# Small_Whole_House_Power_Meter_STPM34_v0_.net
KiCad netlist of a schematic drawn in EAGLE
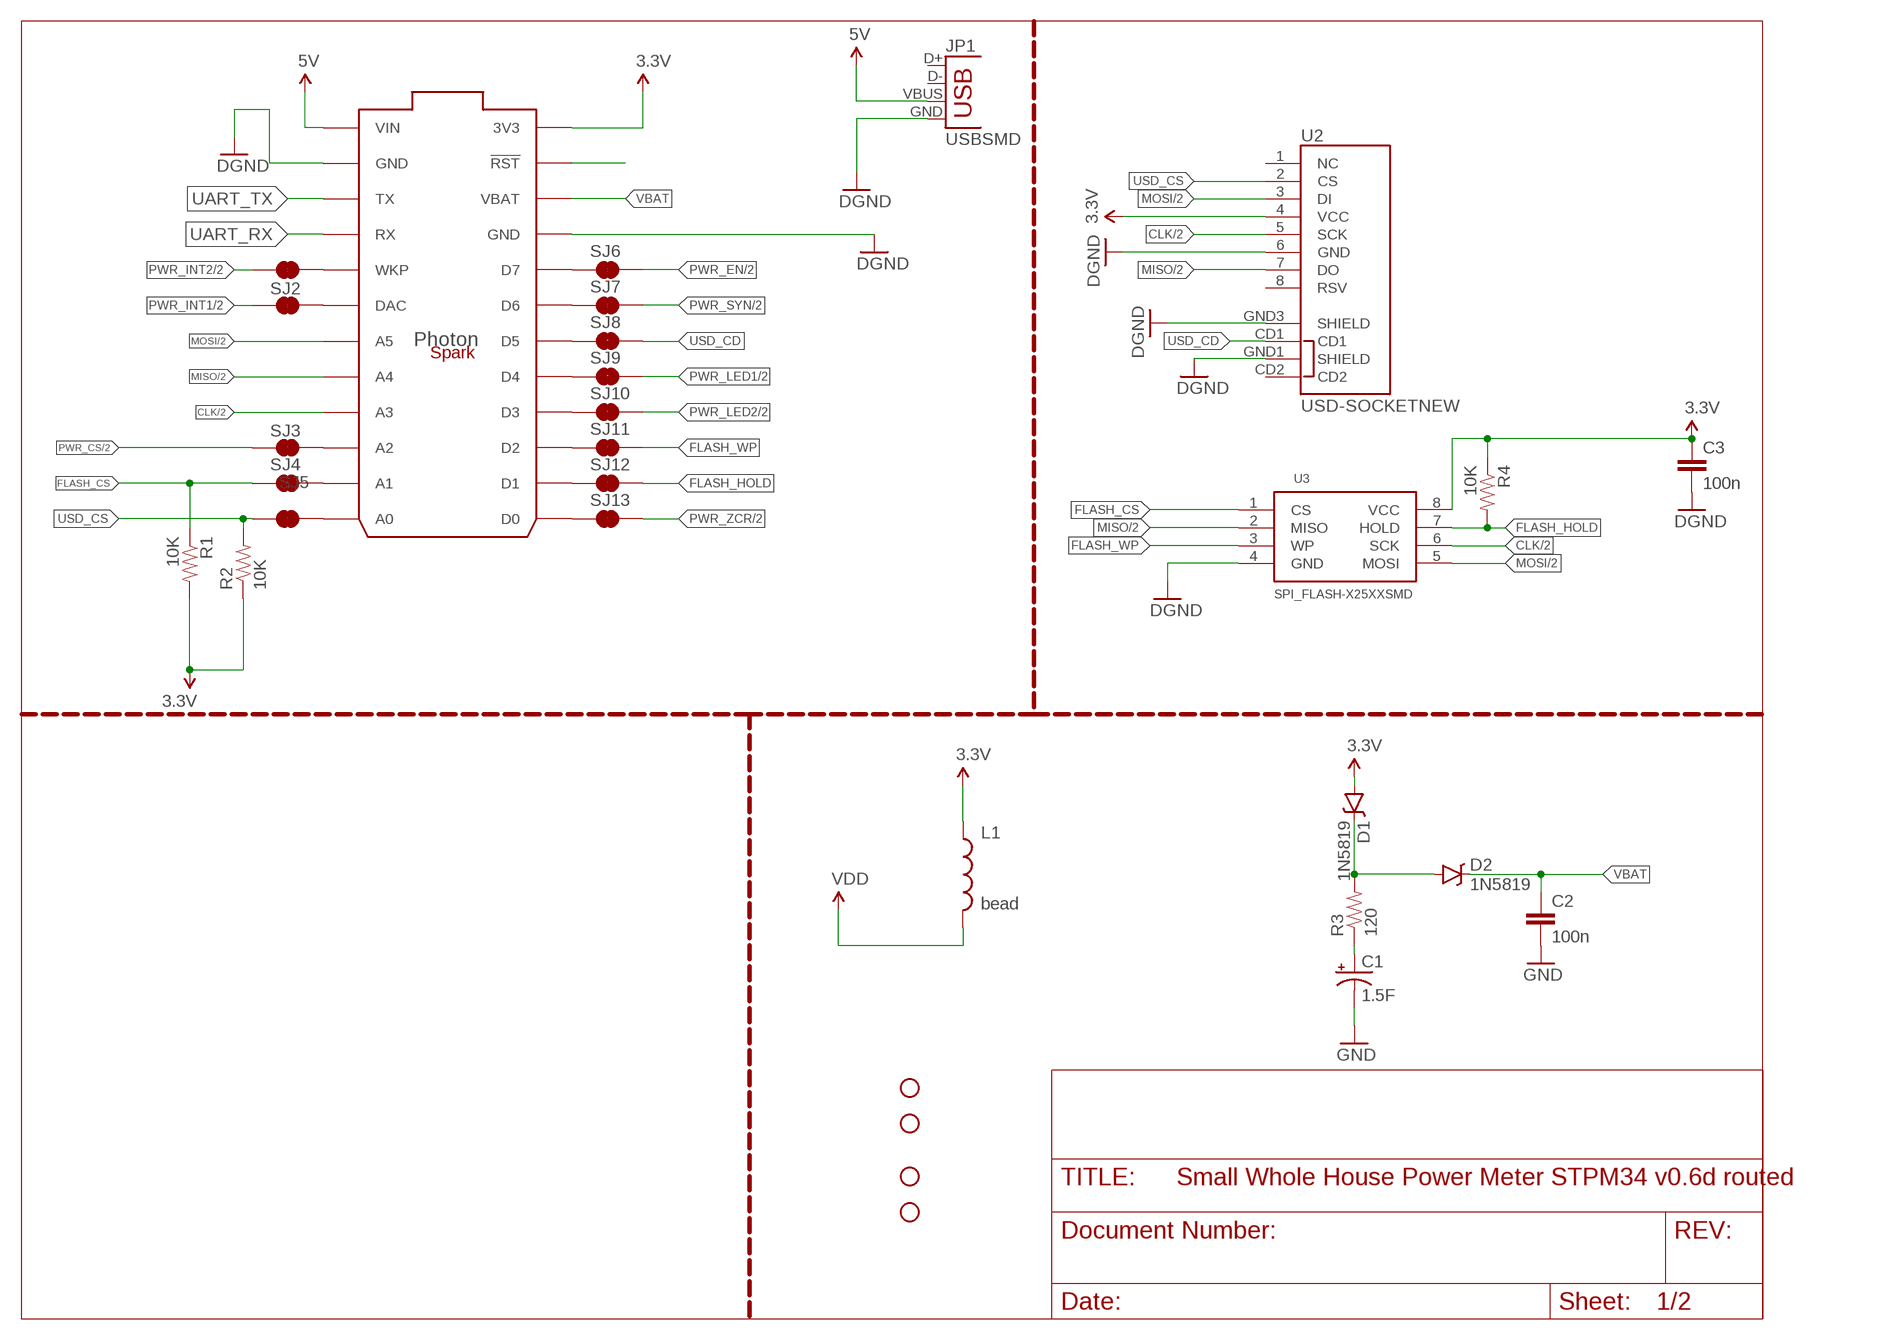
[diagram p0: schematic, sheet 1]
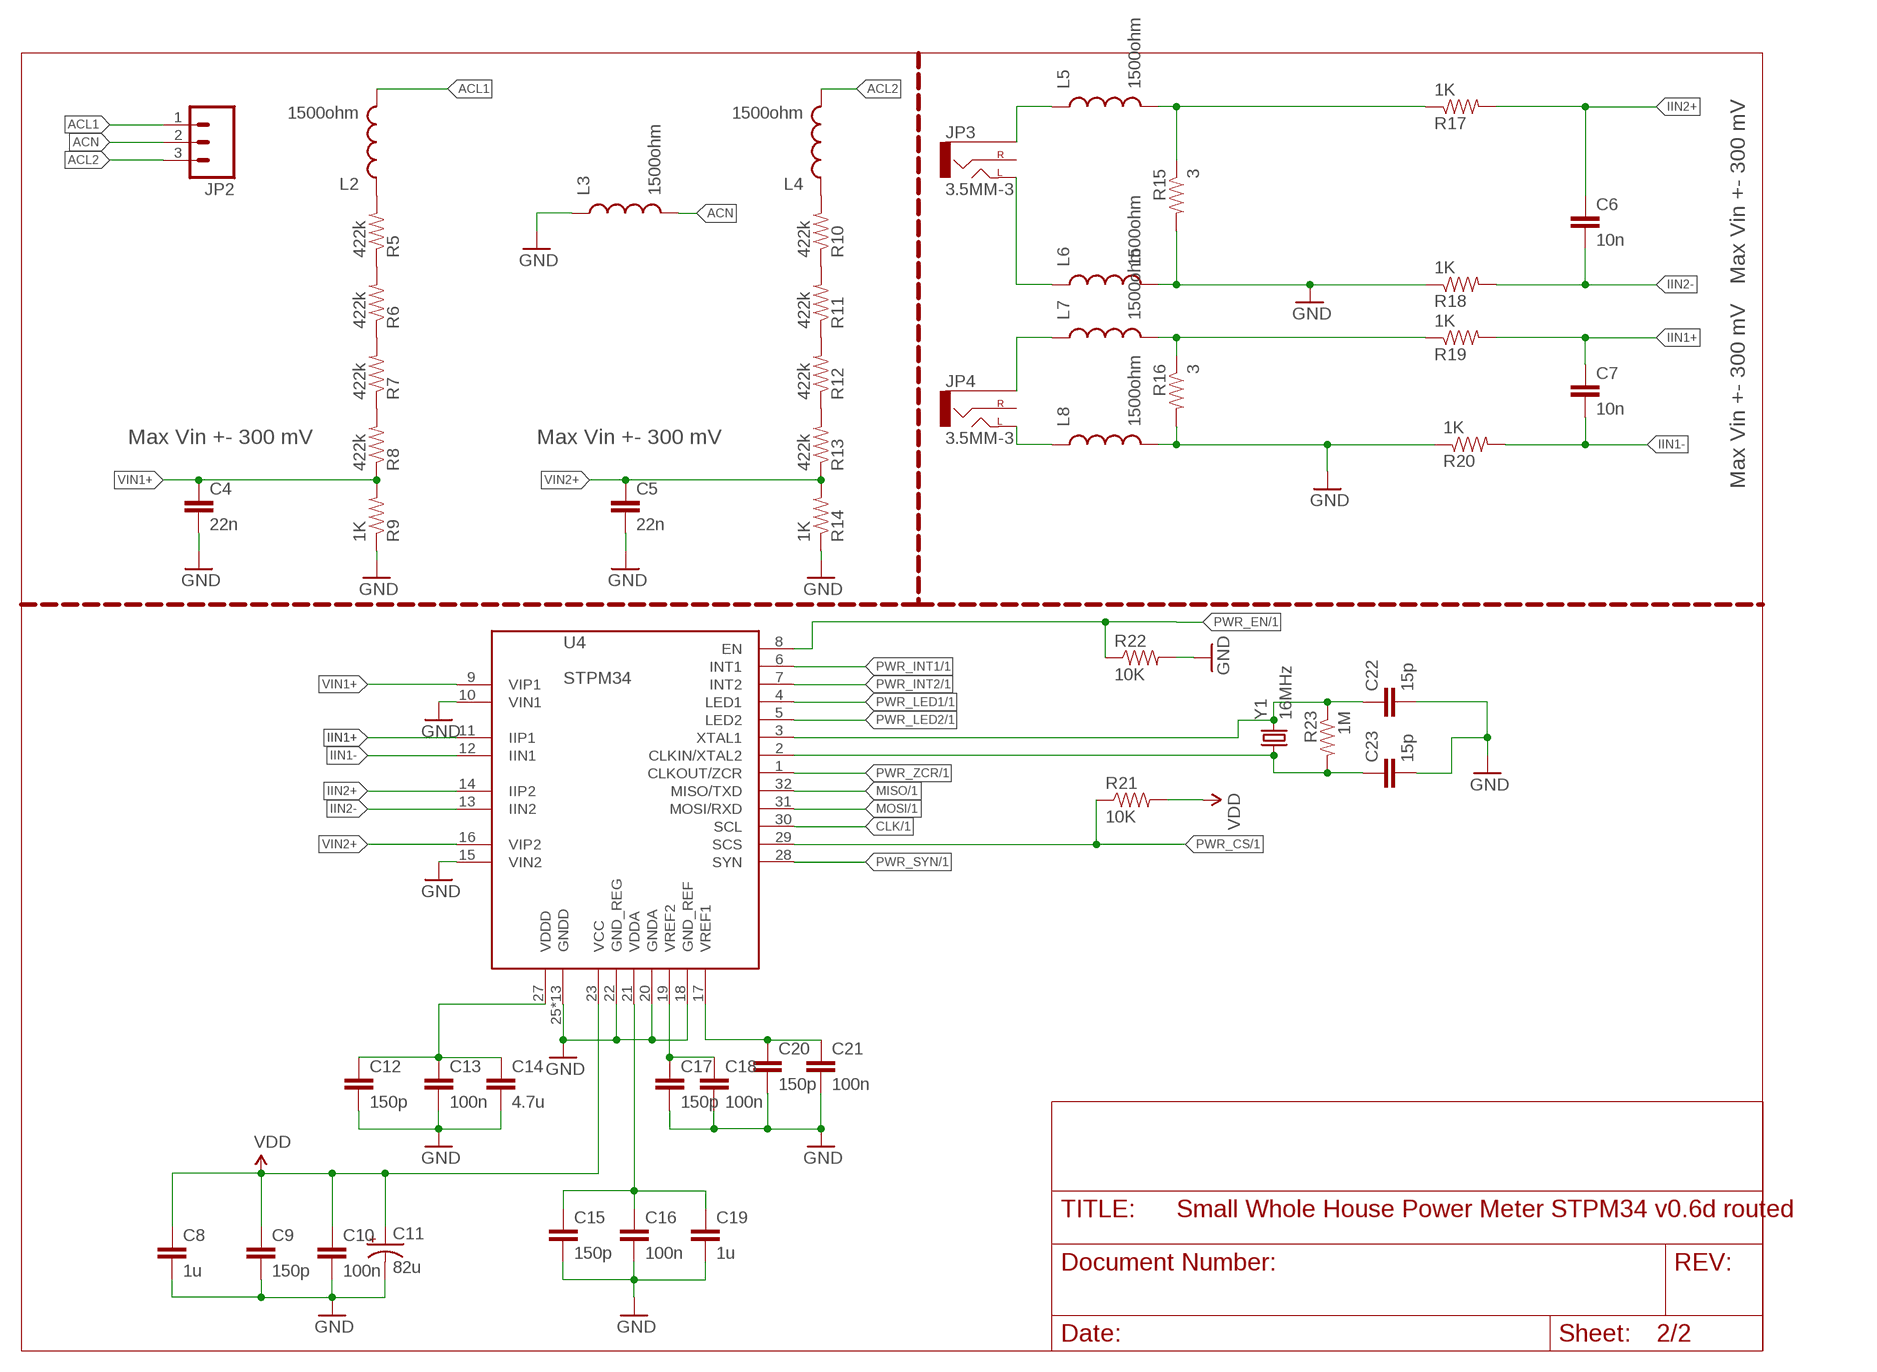
[diagram p1: schematic, sheet 2]

(export (version "E")
  (design (tool "Eeschema 10.0.6"))
  (components
    (comp (ref "C4")
      (value "22n")
      (footprint "eagle-import:0603-CAP")
      (libsource (lib "eagle-import") (part "CAP0603-CAP"))
    )
    (comp (ref "C5")
      (value "22n")
      (footprint "eagle-import:0603-CAP")
      (libsource (lib "eagle-import") (part "CAP0603-CAP"))
    )
    (comp (ref "C6")
      (value "10n")
      (footprint "eagle-import:0603-CAP")
      (libsource (lib "eagle-import") (part "CAP0603-CAP"))
    )
    (comp (ref "C7")
      (value "10n")
      (footprint "eagle-import:0603-CAP")
      (libsource (lib "eagle-import") (part "CAP0603-CAP"))
    )
    (comp (ref "C8")
      (value "1u")
      (footprint "eagle-import:0603-CAP")
      (libsource (lib "eagle-import") (part "CAP0603-CAP"))
    )
    (comp (ref "C9")
      (value "150p")
      (footprint "eagle-import:0603-CAP")
      (libsource (lib "eagle-import") (part "CAP0603-CAP"))
    )
    (comp (ref "C10")
      (value "100n")
      (footprint "eagle-import:0603-CAP")
      (libsource (lib "eagle-import") (part "CAP0603-CAP"))
    )
    (comp (ref "C11")
      (value "82u")
      (footprint "eagle-import:CPOL-RADIAL-10UF-25V")
      (libsource (lib "eagle-import") (part "CAP_POLPTH2"))
    )
    (comp (ref "C12")
      (value "150p")
      (footprint "eagle-import:0603-CAP")
      (libsource (lib "eagle-import") (part "CAP0603-CAP"))
    )
    (comp (ref "C13")
      (value "100n")
      (footprint "eagle-import:0603-CAP")
      (libsource (lib "eagle-import") (part "CAP0603-CAP"))
    )
    (comp (ref "C14")
      (value "4.7u")
      (footprint "eagle-import:0805")
      (libsource (lib "eagle-import") (part "CAP0805"))
    )
    (comp (ref "C15")
      (value "150p")
      (footprint "eagle-import:0603-CAP")
      (libsource (lib "eagle-import") (part "CAP0603-CAP"))
    )
    (comp (ref "C16")
      (value "100n")
      (footprint "eagle-import:0603-CAP")
      (libsource (lib "eagle-import") (part "CAP0603-CAP"))
    )
    (comp (ref "C17")
      (value "150p")
      (footprint "eagle-import:0603-CAP")
      (libsource (lib "eagle-import") (part "CAP0603-CAP"))
    )
    (comp (ref "C18")
      (value "100n")
      (footprint "eagle-import:0603-CAP")
      (libsource (lib "eagle-import") (part "CAP0603-CAP"))
    )
    (comp (ref "C19")
      (value "1u")
      (footprint "eagle-import:0603-CAP")
      (libsource (lib "eagle-import") (part "CAP0603-CAP"))
    )
    (comp (ref "C20")
      (value "150p")
      (footprint "eagle-import:0603-CAP")
      (libsource (lib "eagle-import") (part "CAP0603-CAP"))
    )
    (comp (ref "C21")
      (value "100n")
      (footprint "eagle-import:0603-CAP")
      (libsource (lib "eagle-import") (part "CAP0603-CAP"))
    )
    (comp (ref "C22")
      (value "15p")
      (footprint "eagle-import:0603-CAP")
      (libsource (lib "eagle-import") (part "CAP0603-CAP"))
    )
    (comp (ref "C23")
      (value "15p")
      (footprint "eagle-import:0603-CAP")
      (libsource (lib "eagle-import") (part "CAP0603-CAP"))
    )
    (comp (ref "JP2")
      (value "M03-SCREW-5MM")
      (footprint "eagle-import:SCREWTERMINAL-5MM-3")
      (libsource (lib "eagle-import") (part "M03-SCREW-5MM"))
    )
    (comp (ref "JP3")
      (value "3.5MM-3")
      (footprint "eagle-import:AUDIO-JACK")
      (libsource (lib "eagle-import") (part "AUDIO-JACKPTH"))
    )
    (comp (ref "JP4")
      (value "3.5MM-3")
      (footprint "eagle-import:AUDIO-JACK")
      (libsource (lib "eagle-import") (part "AUDIO-JACKPTH"))
    )
    (comp (ref "L2")
      (value "1500ohm")
      (footprint "eagle-import:0603")
      (libsource (lib "eagle-import") (part "INDUCTOR-SPARKFUN0603"))
    )
    (comp (ref "L3")
      (value "1500ohm")
      (footprint "eagle-import:0603")
      (libsource (lib "eagle-import") (part "INDUCTOR-SPARKFUN0603"))
    )
    (comp (ref "L4")
      (value "1500ohm")
      (footprint "eagle-import:0603")
      (libsource (lib "eagle-import") (part "INDUCTOR-SPARKFUN0603"))
    )
    (comp (ref "L5")
      (value "1500ohm")
      (footprint "eagle-import:0603")
      (libsource (lib "eagle-import") (part "INDUCTOR-SPARKFUN0603"))
    )
    (comp (ref "L6")
      (value "1500ohm")
      (footprint "eagle-import:0603")
      (libsource (lib "eagle-import") (part "INDUCTOR-SPARKFUN0603"))
    )
    (comp (ref "L7")
      (value "1500ohm")
      (footprint "eagle-import:0603")
      (libsource (lib "eagle-import") (part "INDUCTOR-SPARKFUN0603"))
    )
    (comp (ref "L8")
      (value "1500ohm")
      (footprint "eagle-import:0603")
      (libsource (lib "eagle-import") (part "INDUCTOR-SPARKFUN0603"))
    )
    (comp (ref "R5")
      (value "422k")
      (footprint "eagle-import:1206")
      (libsource (lib "eagle-import") (part "RESISTOR1206"))
    )
    (comp (ref "R6")
      (value "422k")
      (footprint "eagle-import:1206")
      (libsource (lib "eagle-import") (part "RESISTOR1206"))
    )
    (comp (ref "R7")
      (value "422k")
      (footprint "eagle-import:1206")
      (libsource (lib "eagle-import") (part "RESISTOR1206"))
    )
    (comp (ref "R8")
      (value "422k")
      (footprint "eagle-import:1206")
      (libsource (lib "eagle-import") (part "RESISTOR1206"))
    )
    (comp (ref "R9")
      (value "1K")
      (footprint "eagle-import:0603-RES")
      (libsource (lib "eagle-import") (part "RESISTOR0603-RES"))
    )
    (comp (ref "R10")
      (value "422k")
      (footprint "eagle-import:1206")
      (libsource (lib "eagle-import") (part "RESISTOR1206"))
    )
    (comp (ref "R11")
      (value "422k")
      (footprint "eagle-import:1206")
      (libsource (lib "eagle-import") (part "RESISTOR1206"))
    )
    (comp (ref "R12")
      (value "422k")
      (footprint "eagle-import:1206")
      (libsource (lib "eagle-import") (part "RESISTOR1206"))
    )
    (comp (ref "R13")
      (value "422k")
      (footprint "eagle-import:1206")
      (libsource (lib "eagle-import") (part "RESISTOR1206"))
    )
    (comp (ref "R14")
      (value "1K")
      (footprint "eagle-import:0603-RES")
      (libsource (lib "eagle-import") (part "RESISTOR0603-RES"))
    )
    (comp (ref "R15")
      (value "3")
      (footprint "eagle-import:0805")
      (libsource (lib "eagle-import") (part "RESISTOR0805-RES"))
    )
    (comp (ref "R16")
      (value "3")
      (footprint "eagle-import:0805")
      (libsource (lib "eagle-import") (part "RESISTOR0805-RES"))
    )
    (comp (ref "R17")
      (value "1K")
      (footprint "eagle-import:0603-RES")
      (libsource (lib "eagle-import") (part "RESISTOR0603-RES"))
    )
    (comp (ref "R18")
      (value "1K")
      (footprint "eagle-import:0603-RES")
      (libsource (lib "eagle-import") (part "RESISTOR0603-RES"))
    )
    (comp (ref "R19")
      (value "1K")
      (footprint "eagle-import:0603-RES")
      (libsource (lib "eagle-import") (part "RESISTOR0603-RES"))
    )
    (comp (ref "R20")
      (value "1K")
      (footprint "eagle-import:0603-RES")
      (libsource (lib "eagle-import") (part "RESISTOR0603-RES"))
    )
    (comp (ref "R21")
      (value "10K")
      (footprint "eagle-import:0603-RES")
      (libsource (lib "eagle-import") (part "RESISTOR0603"))
    )
    (comp (ref "R22")
      (value "10K")
      (footprint "eagle-import:0603-RES")
      (libsource (lib "eagle-import") (part "RESISTOR0603"))
    )
    (comp (ref "R23")
      (value "1M")
      (footprint "eagle-import:0603-RES")
      (libsource (lib "eagle-import") (part "RESISTOR0603-RES"))
    )
    (comp (ref "U4")
      (value "STPM34")
      (footprint "eagle-import:UFQFPN32")
      (libsource (lib "eagle-import") (part "STPM34"))
    )
    (comp (ref "Y1")
      (value "16MHz")
      (footprint "eagle-import:HC49US")
      (libsource (lib "eagle-import") (part "CRYSTALHC49US"))
    )
    (comp (ref "C1")
      (value "1.5F")
      (footprint "eagle-import:1.5SUPERCAPHORIZ")
      (libsource (lib "eagle-import") (part "CAP_POLSUPERHORIZ"))
    )
    (comp (ref "C2")
      (value "100n")
      (footprint "eagle-import:0603-CAP")
      (libsource (lib "eagle-import") (part "CAP0603-CAP"))
    )
    (comp (ref "C3")
      (value "100n")
      (footprint "eagle-import:0603-CAP")
      (libsource (lib "eagle-import") (part "CAP0603-CAP"))
    )
    (comp (ref "D1")
      (value "1N5819")
      (footprint "eagle-import:SOD-123")
      (libsource (lib "eagle-import") (part "DIODE-SCHOTTKY-SOD123"))
    )
    (comp (ref "D2")
      (value "1N5819")
      (footprint "eagle-import:SOD-123")
      (libsource (lib "eagle-import") (part "DIODE-SCHOTTKY-SOD123"))
    )
    (comp (ref "JP1")
      (value "USBSMD")
      (footprint "eagle-import:USB-MINIB")
      (libsource (lib "eagle-import") (part "USBSMD"))
    )
    (comp (ref "L1")
      (value "bead")
      (footprint "eagle-import:0603")
      (libsource (lib "eagle-import") (part "INDUCTOR0603"))
    )
    (comp (ref "M1")
      (value "SPARK_LOGO..")
      (footprint "eagle-import:SPARK_LOGO")
      (libsource (lib "eagle-import") (part "SPARK_LOGO.."))
    )
    (comp (ref "R1")
      (value "10K")
      (footprint "eagle-import:0603-RES")
      (libsource (lib "eagle-import") (part "RESISTOR0603"))
    )
    (comp (ref "R2")
      (value "10K")
      (footprint "eagle-import:0603-RES")
      (libsource (lib "eagle-import") (part "RESISTOR0603"))
    )
    (comp (ref "R3")
      (value "120")
      (footprint "eagle-import:0603-RES")
      (libsource (lib "eagle-import") (part "RESISTOR0603"))
    )
    (comp (ref "R4")
      (value "10K")
      (footprint "eagle-import:0603-RES")
      (libsource (lib "eagle-import") (part "RESISTOR0603"))
    )
    (comp (ref "SJ1")
      (value "JUMPER-PAD-2-NC_BY_TRACE")
      (footprint "eagle-import:PAD-JUMPER-2-NC_BY_TRACE_YES_SILK")
      (libsource (lib "eagle-import") (part "JUMPER-PAD-2-NC_BY_TRACE"))
    )
    (comp (ref "SJ2")
      (value "JUMPER-PAD-2-NC_BY_TRACE")
      (footprint "eagle-import:PAD-JUMPER-2-NC_BY_TRACE_YES_SILK")
      (libsource (lib "eagle-import") (part "JUMPER-PAD-2-NC_BY_TRACE"))
    )
    (comp (ref "SJ3")
      (value "JUMPER-PAD-2-NC_BY_TRACE")
      (footprint "eagle-import:PAD-JUMPER-2-NC_BY_TRACE_YES_SILK")
      (libsource (lib "eagle-import") (part "JUMPER-PAD-2-NC_BY_TRACE"))
    )
    (comp (ref "SJ4")
      (value "JUMPER-PAD-2-NC_BY_TRACE")
      (footprint "eagle-import:PAD-JUMPER-2-NC_BY_TRACE_YES_SILK")
      (libsource (lib "eagle-import") (part "JUMPER-PAD-2-NC_BY_TRACE"))
    )
    (comp (ref "SJ5")
      (value "JUMPER-PAD-2-NC_BY_TRACE")
      (footprint "eagle-import:PAD-JUMPER-2-NC_BY_TRACE_YES_SILK")
      (libsource (lib "eagle-import") (part "JUMPER-PAD-2-NC_BY_TRACE"))
    )
    (comp (ref "SJ6")
      (value "JUMPER-PAD-2-NC_BY_TRACE")
      (footprint "eagle-import:PAD-JUMPER-2-NC_BY_TRACE_YES_SILK")
      (libsource (lib "eagle-import") (part "JUMPER-PAD-2-NC_BY_TRACE"))
    )
    (comp (ref "SJ7")
      (value "JUMPER-PAD-2-NC_BY_TRACE")
      (footprint "eagle-import:PAD-JUMPER-2-NC_BY_TRACE_YES_SILK")
      (libsource (lib "eagle-import") (part "JUMPER-PAD-2-NC_BY_TRACE"))
    )
    (comp (ref "SJ8")
      (value "JUMPER-PAD-2-NC_BY_TRACE")
      (footprint "eagle-import:PAD-JUMPER-2-NC_BY_TRACE_YES_SILK")
      (libsource (lib "eagle-import") (part "JUMPER-PAD-2-NC_BY_TRACE"))
    )
    (comp (ref "SJ9")
      (value "JUMPER-PAD-2-NC_BY_TRACE")
      (footprint "eagle-import:PAD-JUMPER-2-NC_BY_TRACE_YES_SILK")
      (libsource (lib "eagle-import") (part "JUMPER-PAD-2-NC_BY_TRACE"))
    )
    (comp (ref "SJ10")
      (value "JUMPER-PAD-2-NC_BY_TRACE")
      (footprint "eagle-import:PAD-JUMPER-2-NC_BY_TRACE_YES_SILK")
      (libsource (lib "eagle-import") (part "JUMPER-PAD-2-NC_BY_TRACE"))
    )
    (comp (ref "SJ11")
      (value "JUMPER-PAD-2-NC_BY_TRACE")
      (footprint "eagle-import:PAD-JUMPER-2-NC_BY_TRACE_YES_SILK")
      (libsource (lib "eagle-import") (part "JUMPER-PAD-2-NC_BY_TRACE"))
    )
    (comp (ref "SJ12")
      (value "JUMPER-PAD-2-NC_BY_TRACE")
      (footprint "eagle-import:PAD-JUMPER-2-NC_BY_TRACE_YES_SILK")
      (libsource (lib "eagle-import") (part "JUMPER-PAD-2-NC_BY_TRACE"))
    )
    (comp (ref "SJ13")
      (value "JUMPER-PAD-2-NC_BY_TRACE")
      (footprint "eagle-import:PAD-JUMPER-2-NC_BY_TRACE_YES_SILK")
      (libsource (lib "eagle-import") (part "JUMPER-PAD-2-NC_BY_TRACE"))
    )
    (comp (ref "STANDOFF1")
      (value "STAND-OFF")
      (footprint "eagle-import:STAND-OFF")
      (libsource (lib "eagle-import") (part "STAND-OFF"))
    )
    (comp (ref "STANDOFF2")
      (value "STAND-OFF")
      (footprint "eagle-import:STAND-OFF")
      (libsource (lib "eagle-import") (part "STAND-OFF"))
    )
    (comp (ref "STANDOFF3")
      (value "STAND-OFF")
      (footprint "eagle-import:STAND-OFF")
      (libsource (lib "eagle-import") (part "STAND-OFF"))
    )
    (comp (ref "STANDOFF4")
      (value "STAND-OFF")
      (footprint "eagle-import:STAND-OFF")
      (libsource (lib "eagle-import") (part "STAND-OFF"))
    )
    (comp (ref "U1")
      (value "PHOTON_SMD_W_PINS")
      (footprint "eagle-import:PHOTON_SMD_W_PINS")
      (libsource (lib "eagle-import") (part "PHOTON_SMD_W_PINS"))
    )
    (comp (ref "U2")
      (value "USD-SOCKETNEW")
      (footprint "eagle-import:MICRO-SD-SOCKET-PP")
      (libsource (lib "eagle-import") (part "USD-SOCKETNEW"))
    )
    (comp (ref "U3")
      (value "SPI_FLASH-X25XXSMD")
      (footprint "eagle-import:SO08N_W")
      (libsource (lib "eagle-import") (part "SPI_FLASH-X25XXSMD"))
    )
  )
  (nets
    (net (code "1") (name "3.3V") (class "Default")
      (node (ref "C3") (pin "1") (pinfunction "1_1") (pintype "passive"))
      (node (ref "D1") (pin "A") (pinfunction "A_A") (pintype "passive"))
      (node (ref "L1") (pin "1") (pinfunction "1_1") (pintype "passive"))
      (node (ref "R1") (pin "2") (pinfunction "2_2") (pintype "passive"))
      (node (ref "R2") (pin "1") (pinfunction "1_1") (pintype "passive"))
      (node (ref "R4") (pin "1") (pinfunction "1_1") (pintype "passive"))
      (node (ref "U1") (pin "1_24") (pinfunction "3V3_1_24") (pintype "power_in"))
      (node (ref "U1") (pin "24") (pinfunction "3V3_24") (pintype "power_in"))
      (node (ref "U1") (pin "24*") (pinfunction "3V3_24*") (pintype "power_in"))
      (node (ref "U1") (pin "24_") (pinfunction "3V3_24_") (pintype "power_in"))
      (node (ref "U2") (pin "4") (pinfunction "VCC_4") (pintype "bidirectional"))
      (node (ref "U3") (pin "8") (pinfunction "VCC_8") (pintype "bidirectional"))
    )
    (net (code "2") (name "5V") (class "Default")
      (node (ref "JP1") (pin "VBUS") (pinfunction "VBUS_VBUS") (pintype "bidirectional"))
      (node (ref "U1") (pin "1") (pinfunction "VIN_1") (pintype "power_in"))
      (node (ref "U1") (pin "1*") (pinfunction "VIN_1*") (pintype "power_in"))
      (node (ref "U1") (pin "1_") (pinfunction "VIN_1_") (pintype "power_in"))
      (node (ref "U1") (pin "1_1") (pinfunction "VIN_1_1") (pintype "power_in"))
    )
    (net (code "3") (name "ACL1") (class "Default")
      (node (ref "JP2") (pin "1") (pinfunction "1_1") (pintype "passive"))
      (node (ref "L2") (pin "2") (pinfunction "2_2") (pintype "passive"))
    )
    (net (code "4") (name "ACL2") (class "Default")
      (node (ref "JP2") (pin "3") (pinfunction "3_3") (pintype "passive"))
      (node (ref "L4") (pin "2") (pinfunction "2_2") (pintype "passive"))
    )
    (net (code "5") (name "ACN") (class "Default")
      (node (ref "JP2") (pin "2") (pinfunction "2_2") (pintype "passive"))
      (node (ref "L3") (pin "2") (pinfunction "2_2") (pintype "passive"))
    )
    (net (code "6") (name "CLK") (class "Default")
      (node (ref "U1") (pin "1_9") (pinfunction "A3_1_9") (pintype "bidirectional"))
      (node (ref "U1") (pin "9") (pinfunction "A3_9") (pintype "bidirectional"))
      (node (ref "U1") (pin "9*") (pinfunction "A3_9*") (pintype "bidirectional"))
      (node (ref "U1") (pin "9_") (pinfunction "A3_9_") (pintype "bidirectional"))
      (node (ref "U2") (pin "5") (pinfunction "SCK_5") (pintype "bidirectional"))
      (node (ref "U3") (pin "6") (pinfunction "SCK_6") (pintype "bidirectional"))
      (node (ref "U4") (pin "30") (pinfunction "SCL_30") (pintype "bidirectional"))
    )
    (net (code "7") (name "FLASH_CS") (class "Default")
      (node (ref "R1") (pin "1") (pinfunction "1_1") (pintype "passive"))
      (node (ref "SJ4") (pin "1") (pinfunction "1_1") (pintype "passive"))
      (node (ref "U3") (pin "1") (pinfunction "CS_1") (pintype "bidirectional"))
    )
    (net (code "8") (name "FLASH_HOLD") (class "Default")
      (node (ref "R4") (pin "2") (pinfunction "2_2") (pintype "passive"))
      (node (ref "SJ12") (pin "2") (pinfunction "2_2") (pintype "passive"))
      (node (ref "U3") (pin "7") (pinfunction "HOLD_7") (pintype "bidirectional"))
    )
    (net (code "9") (name "FLASH_WP") (class "Default")
      (node (ref "SJ11") (pin "2") (pinfunction "2_2") (pintype "passive"))
      (node (ref "U3") (pin "3") (pinfunction "WP_3") (pintype "bidirectional"))
    )
    (net (code "10") (name "GND") (class "Default")
      (node (ref "C1") (pin "-") (pinfunction "-_-") (pintype "passive"))
      (node (ref "C10") (pin "2") (pinfunction "2_2") (pintype "passive"))
      (node (ref "C11") (pin "2") (pinfunction "-_2") (pintype "passive"))
      (node (ref "C12") (pin "2") (pinfunction "2_2") (pintype "passive"))
      (node (ref "C13") (pin "2") (pinfunction "2_2") (pintype "passive"))
      (node (ref "C14") (pin "2") (pinfunction "2_2") (pintype "passive"))
      (node (ref "C15") (pin "2") (pinfunction "2_2") (pintype "passive"))
      (node (ref "C16") (pin "2") (pinfunction "2_2") (pintype "passive"))
      (node (ref "C17") (pin "2") (pinfunction "2_2") (pintype "passive"))
      (node (ref "C18") (pin "2") (pinfunction "2_2") (pintype "passive"))
      (node (ref "C19") (pin "2") (pinfunction "2_2") (pintype "passive"))
      (node (ref "C2") (pin "2") (pinfunction "2_2") (pintype "passive"))
      (node (ref "C20") (pin "2") (pinfunction "2_2") (pintype "passive"))
      (node (ref "C21") (pin "2") (pinfunction "2_2") (pintype "passive"))
      (node (ref "C22") (pin "2") (pinfunction "2_2") (pintype "passive"))
      (node (ref "C23") (pin "2") (pinfunction "2_2") (pintype "passive"))
      (node (ref "C3") (pin "2") (pinfunction "2_2") (pintype "passive"))
      (node (ref "C4") (pin "2") (pinfunction "2_2") (pintype "passive"))
      (node (ref "C5") (pin "2") (pinfunction "2_2") (pintype "passive"))
      (node (ref "C8") (pin "2") (pinfunction "2_2") (pintype "passive"))
      (node (ref "C9") (pin "2") (pinfunction "2_2") (pintype "passive"))
      (node (ref "JP1") (pin "GND") (pinfunction "GND_GND") (pintype "bidirectional"))
      (node (ref "L3") (pin "1") (pinfunction "1_1") (pintype "passive"))
      (node (ref "L6") (pin "2") (pinfunction "2_2") (pintype "passive"))
      (node (ref "L8") (pin "2") (pinfunction "2_2") (pintype "passive"))
      (node (ref "R14") (pin "1") (pinfunction "1_1") (pintype "passive"))
      (node (ref "R15") (pin "2") (pinfunction "2_2") (pintype "passive"))
      (node (ref "R16") (pin "2") (pinfunction "2_2") (pintype "passive"))
      (node (ref "R18") (pin "1") (pinfunction "1_1") (pintype "passive"))
      (node (ref "R20") (pin "1") (pinfunction "1_1") (pintype "passive"))
      (node (ref "R22") (pin "2") (pinfunction "2_2") (pintype "passive"))
      (node (ref "R9") (pin "1") (pinfunction "1_1") (pintype "passive"))
      (node (ref "U1") (pin "1_2") (pinfunction "GND_1_2") (pintype "power_in"))
      (node (ref "U1") (pin "1_21") (pinfunction "GND_1_21") (pintype "power_in"))
      (node (ref "U1") (pin "2") (pinfunction "GND_2") (pintype "power_in"))
      (node (ref "U1") (pin "2*") (pinfunction "GND_2*") (pintype "power_in"))
      (node (ref "U1") (pin "21") (pinfunction "GND_21") (pintype "power_in"))
      (node (ref "U1") (pin "21*") (pinfunction "GND_21*") (pintype "power_in"))
      (node (ref "U1") (pin "21_") (pinfunction "GND_21_") (pintype "power_in"))
      (node (ref "U1") (pin "2_") (pinfunction "GND_2_") (pintype "power_in"))
      (node (ref "U2") (pin "6") (pinfunction "GND_6") (pintype "bidirectional"))
      (node (ref "U2") (pin "GND1") (pinfunction "SHIELD_GND1") (pintype "bidirectional"))
      (node (ref "U2") (pin "GND3") (pinfunction "SHIELD_GND3") (pintype "bidirectional"))
      (node (ref "U3") (pin "4") (pinfunction "GND_4") (pintype "bidirectional"))
      (node (ref "U4") (pin "10") (pinfunction "VIN1_10") (pintype "bidirectional"))
      (node (ref "U4") (pin "15") (pinfunction "VIN2_15") (pintype "bidirectional"))
      (node (ref "U4") (pin "18") (pinfunction "GND_REF_18") (pintype "bidirectional"))
      (node (ref "U4") (pin "20") (pinfunction "GNDA_20") (pintype "bidirectional"))
      (node (ref "U4") (pin "22") (pinfunction "GND_REG_22") (pintype "bidirectional"))
      (node (ref "U4") (pin "25") (pinfunction "GNDD_25") (pintype "bidirectional"))
      (node (ref "U4") (pin "26") (pinfunction "GNDD_26") (pintype "bidirectional"))
      (node (ref "U4") (pin "EXP") (pinfunction "GNDD_EXP") (pintype "bidirectional"))
      (node (ref "U4") (pin "EXP1") (pinfunction "GNDD_EXP1") (pintype "bidirectional"))
      (node (ref "U4") (pin "P$1") (pinfunction "GNDD_P$1") (pintype "bidirectional"))
      (node (ref "U4") (pin "P$2") (pinfunction "GNDD_P$2") (pintype "bidirectional"))
      (node (ref "U4") (pin "P$3") (pinfunction "GNDD_P$3") (pintype "bidirectional"))
      (node (ref "U4") (pin "P$4") (pinfunction "GNDD_P$4") (pintype "bidirectional"))
      (node (ref "U4") (pin "P$5") (pinfunction "GNDD_P$5") (pintype "bidirectional"))
      (node (ref "U4") (pin "P$6") (pinfunction "GNDD_P$6") (pintype "bidirectional"))
      (node (ref "U4") (pin "P$7") (pinfunction "GNDD_P$7") (pintype "bidirectional"))
      (node (ref "U4") (pin "P$8") (pinfunction "GNDD_P$8") (pintype "bidirectional"))
      (node (ref "U4") (pin "P$9") (pinfunction "GNDD_P$9") (pintype "bidirectional"))
    )
    (net (code "11") (name "IIN1+") (class "Default")
      (node (ref "C7") (pin "1") (pinfunction "1_1") (pintype "passive"))
      (node (ref "R19") (pin "2") (pinfunction "2_2") (pintype "passive"))
      (node (ref "U4") (pin "11") (pinfunction "IIP1_11") (pintype "bidirectional"))
    )
    (net (code "12") (name "IIN1-") (class "Default")
      (node (ref "C7") (pin "2") (pinfunction "2_2") (pintype "passive"))
      (node (ref "R20") (pin "2") (pinfunction "2_2") (pintype "passive"))
      (node (ref "U4") (pin "12") (pinfunction "IIN1_12") (pintype "bidirectional"))
    )
    (net (code "13") (name "IIN2+") (class "Default")
      (node (ref "C6") (pin "1") (pinfunction "1_1") (pintype "passive"))
      (node (ref "R17") (pin "2") (pinfunction "2_2") (pintype "passive"))
      (node (ref "U4") (pin "14") (pinfunction "IIP2_14") (pintype "bidirectional"))
    )
    (net (code "14") (name "IIN2-") (class "Default")
      (node (ref "C6") (pin "2") (pinfunction "2_2") (pintype "passive"))
      (node (ref "R18") (pin "2") (pinfunction "2_2") (pintype "passive"))
      (node (ref "U4") (pin "13") (pinfunction "IIN2_13") (pintype "bidirectional"))
    )
    (net (code "15") (name "MISO") (class "Default")
      (node (ref "U1") (pin "1_8") (pinfunction "A4_1_8") (pintype "bidirectional"))
      (node (ref "U1") (pin "8") (pinfunction "A4_8") (pintype "bidirectional"))
      (node (ref "U1") (pin "8*") (pinfunction "A4_8*") (pintype "bidirectional"))
      (node (ref "U1") (pin "8_") (pinfunction "A4_8_") (pintype "bidirectional"))
      (node (ref "U2") (pin "7") (pinfunction "DO_7") (pintype "bidirectional"))
      (node (ref "U3") (pin "2") (pinfunction "MISO_2") (pintype "bidirectional"))
      (node (ref "U4") (pin "32") (pinfunction "MISO/TXD_32") (pintype "bidirectional"))
    )
    (net (code "16") (name "MOSI") (class "Default")
      (node (ref "U1") (pin "1_7") (pinfunction "A5_1_7") (pintype "bidirectional"))
      (node (ref "U1") (pin "7") (pinfunction "A5_7") (pintype "bidirectional"))
      (node (ref "U1") (pin "7*") (pinfunction "A5_7*") (pintype "bidirectional"))
      (node (ref "U1") (pin "7_") (pinfunction "A5_7_") (pintype "bidirectional"))
      (node (ref "U2") (pin "3") (pinfunction "DI_3") (pintype "bidirectional"))
      (node (ref "U3") (pin "5") (pinfunction "MOSI_5") (pintype "bidirectional"))
      (node (ref "U4") (pin "31") (pinfunction "MOSI/RXD_31") (pintype "bidirectional"))
    )
    (net (code "17") (name "Net-(C1-Pad+)") (class "Default")
      (node (ref "C1") (pin "+") (pinfunction "+_+") (pintype "passive"))
      (node (ref "R3") (pin "1") (pinfunction "1_1") (pintype "passive"))
    )
    (net (code "18") (name "Net-(D1-PadC)") (class "Default")
      (node (ref "D1") (pin "C") (pinfunction "C_C") (pintype "passive"))
      (node (ref "D2") (pin "A") (pinfunction "A_A") (pintype "passive"))
      (node (ref "R3") (pin "2") (pinfunction "2_2") (pintype "passive"))
    )
    (net (code "19") (name "Net-(JP3-LEFT)") (class "Default")
      (node (ref "JP3") (pin "TIP") (pinfunction "LEFT_TIP") (pintype "bidirectional"))
      (node (ref "L6") (pin "1") (pinfunction "1_1") (pintype "passive"))
    )
    (net (code "20") (name "Net-(JP3-PadSLEEVE)") (class "Default")
      (node (ref "JP3") (pin "SLEEVE") (pinfunction "SLEEVE_SLEEVE") (pintype "bidirectional"))
      (node (ref "L5") (pin "1") (pinfunction "1_1") (pintype "passive"))
    )
    (net (code "21") (name "Net-(JP4-LEFT)") (class "Default")
      (node (ref "JP4") (pin "TIP") (pinfunction "LEFT_TIP") (pintype "bidirectional"))
      (node (ref "L8") (pin "1") (pinfunction "1_1") (pintype "passive"))
    )
    (net (code "22") (name "Net-(JP4-PadSLEEVE)") (class "Default")
      (node (ref "JP4") (pin "SLEEVE") (pinfunction "SLEEVE_SLEEVE") (pintype "bidirectional"))
      (node (ref "L7") (pin "1") (pinfunction "1_1") (pintype "passive"))
    )
    (net (code "23") (name "Net-(L2-Pad1)") (class "Default")
      (node (ref "L2") (pin "1") (pinfunction "1_1") (pintype "passive"))
      (node (ref "R5") (pin "2") (pinfunction "2_2") (pintype "passive"))
    )
    (net (code "24") (name "Net-(L4-Pad1)") (class "Default")
      (node (ref "L4") (pin "1") (pinfunction "1_1") (pintype "passive"))
      (node (ref "R10") (pin "2") (pinfunction "2_2") (pintype "passive"))
    )
    (net (code "25") (name "Net-(L5-Pad2)") (class "Default")
      (node (ref "L5") (pin "2") (pinfunction "2_2") (pintype "passive"))
      (node (ref "R15") (pin "1") (pinfunction "1_1") (pintype "passive"))
      (node (ref "R17") (pin "1") (pinfunction "1_1") (pintype "passive"))
    )
    (net (code "26") (name "Net-(L7-Pad2)") (class "Default")
      (node (ref "L7") (pin "2") (pinfunction "2_2") (pintype "passive"))
      (node (ref "R16") (pin "1") (pinfunction "1_1") (pintype "passive"))
      (node (ref "R19") (pin "1") (pinfunction "1_1") (pintype "passive"))
    )
    (net (code "27") (name "Net-(R5-Pad1)") (class "Default")
      (node (ref "R5") (pin "1") (pinfunction "1_1") (pintype "passive"))
      (node (ref "R6") (pin "2") (pinfunction "2_2") (pintype "passive"))
    )
    (net (code "28") (name "Net-(R6-Pad1)") (class "Default")
      (node (ref "R6") (pin "1") (pinfunction "1_1") (pintype "passive"))
      (node (ref "R7") (pin "2") (pinfunction "2_2") (pintype "passive"))
    )
    (net (code "29") (name "Net-(R7-Pad1)") (class "Default")
      (node (ref "R7") (pin "1") (pinfunction "1_1") (pintype "passive"))
      (node (ref "R8") (pin "2") (pinfunction "2_2") (pintype "passive"))
    )
    (net (code "30") (name "Net-(R10-Pad1)") (class "Default")
      (node (ref "R10") (pin "1") (pinfunction "1_1") (pintype "passive"))
      (node (ref "R11") (pin "2") (pinfunction "2_2") (pintype "passive"))
    )
    (net (code "31") (name "Net-(R11-Pad1)") (class "Default")
      (node (ref "R11") (pin "1") (pinfunction "1_1") (pintype "passive"))
      (node (ref "R12") (pin "2") (pinfunction "2_2") (pintype "passive"))
    )
    (net (code "32") (name "Net-(R12-Pad1)") (class "Default")
      (node (ref "R12") (pin "1") (pinfunction "1_1") (pintype "passive"))
      (node (ref "R13") (pin "2") (pinfunction "2_2") (pintype "passive"))
    )
    (net (code "33") (name "Net-(SJ1-Pad2)") (class "Default")
      (node (ref "SJ1") (pin "2") (pinfunction "2_2") (pintype "passive"))
      (node (ref "U1") (pin "1_5") (pinfunction "WKP_1_5") (pintype "bidirectional"))
      (node (ref "U1") (pin "5") (pinfunction "WKP_5") (pintype "bidirectional"))
      (node (ref "U1") (pin "5*") (pinfunction "WKP_5*") (pintype "bidirectional"))
      (node (ref "U1") (pin "5_") (pinfunction "WKP_5_") (pintype "bidirectional"))
    )
    (net (code "34") (name "Net-(SJ2-Pad2)") (class "Default")
      (node (ref "SJ2") (pin "2") (pinfunction "2_2") (pintype "passive"))
      (node (ref "U1") (pin "1_6") (pinfunction "DAC_1_6") (pintype "bidirectional"))
      (node (ref "U1") (pin "6") (pinfunction "DAC_6") (pintype "bidirectional"))
      (node (ref "U1") (pin "6*") (pinfunction "DAC_6*") (pintype "bidirectional"))
      (node (ref "U1") (pin "6_") (pinfunction "DAC_6_") (pintype "bidirectional"))
    )
    (net (code "35") (name "Net-(SJ3-Pad2)") (class "Default")
      (node (ref "SJ3") (pin "2") (pinfunction "2_2") (pintype "passive"))
      (node (ref "U1") (pin "10") (pinfunction "A2_10") (pintype "bidirectional"))
      (node (ref "U1") (pin "10*") (pinfunction "A2_10*") (pintype "bidirectional"))
      (node (ref "U1") (pin "10_") (pinfunction "A2_10_") (pintype "bidirectional"))
      (node (ref "U1") (pin "1_10") (pinfunction "A2_1_10") (pintype "bidirectional"))
    )
    (net (code "36") (name "Net-(SJ4-Pad2)") (class "Default")
      (node (ref "SJ4") (pin "2") (pinfunction "2_2") (pintype "passive"))
      (node (ref "U1") (pin "11") (pinfunction "A1_11") (pintype "bidirectional"))
      (node (ref "U1") (pin "11*") (pinfunction "A1_11*") (pintype "bidirectional"))
      (node (ref "U1") (pin "11_") (pinfunction "A1_11_") (pintype "bidirectional"))
      (node (ref "U1") (pin "1_11") (pinfunction "A1_1_11") (pintype "bidirectional"))
    )
    (net (code "37") (name "Net-(SJ5-Pad2)") (class "Default")
      (node (ref "SJ5") (pin "2") (pinfunction "2_2") (pintype "passive"))
      (node (ref "U1") (pin "12") (pinfunction "A0_12") (pintype "bidirectional"))
      (node (ref "U1") (pin "12*") (pinfunction "A0_12*") (pintype "bidirectional"))
      (node (ref "U1") (pin "12_") (pinfunction "A0_12_") (pintype "bidirectional"))
      (node (ref "U1") (pin "1_12") (pinfunction "A0_1_12") (pintype "bidirectional"))
    )
    (net (code "38") (name "Net-(SJ6-Pad1)") (class "Default")
      (node (ref "SJ6") (pin "1") (pinfunction "1_1") (pintype "passive"))
      (node (ref "U1") (pin "1_20") (pinfunction "D7_1_20") (pintype "bidirectional"))
      (node (ref "U1") (pin "20") (pinfunction "D7_20") (pintype "bidirectional"))
      (node (ref "U1") (pin "20*") (pinfunction "D7_20*") (pintype "bidirectional"))
      (node (ref "U1") (pin "20_") (pinfunction "D7_20_") (pintype "bidirectional"))
    )
    (net (code "39") (name "Net-(SJ7-Pad1)") (class "Default")
      (node (ref "SJ7") (pin "1") (pinfunction "1_1") (pintype "passive"))
      (node (ref "U1") (pin "19") (pinfunction "D6_19") (pintype "bidirectional"))
      (node (ref "U1") (pin "19*") (pinfunction "D6_19*") (pintype "bidirectional"))
      (node (ref "U1") (pin "19_") (pinfunction "D6_19_") (pintype "bidirectional"))
      (node (ref "U1") (pin "1_19") (pinfunction "D6_1_19") (pintype "bidirectional"))
    )
    (net (code "40") (name "Net-(SJ8-Pad1)") (class "Default")
      (node (ref "SJ8") (pin "1") (pinfunction "1_1") (pintype "passive"))
      (node (ref "U1") (pin "18") (pinfunction "D5_18") (pintype "bidirectional"))
      (node (ref "U1") (pin "18*") (pinfunction "D5_18*") (pintype "bidirectional"))
      (node (ref "U1") (pin "18_") (pinfunction "D5_18_") (pintype "bidirectional"))
      (node (ref "U1") (pin "1_18") (pinfunction "D5_1_18") (pintype "bidirectional"))
    )
    (net (code "41") (name "Net-(SJ9-Pad1)") (class "Default")
      (node (ref "SJ9") (pin "1") (pinfunction "1_1") (pintype "passive"))
      (node (ref "U1") (pin "17") (pinfunction "D4_17") (pintype "bidirectional"))
      (node (ref "U1") (pin "17*") (pinfunction "D4_17*") (pintype "bidirectional"))
      (node (ref "U1") (pin "17_") (pinfunction "D4_17_") (pintype "bidirectional"))
      (node (ref "U1") (pin "1_17") (pinfunction "D4_1_17") (pintype "bidirectional"))
    )
    (net (code "42") (name "Net-(SJ10-Pad1)") (class "Default")
      (node (ref "SJ10") (pin "1") (pinfunction "1_1") (pintype "passive"))
      (node (ref "U1") (pin "16") (pinfunction "D3_16") (pintype "bidirectional"))
      (node (ref "U1") (pin "16*") (pinfunction "D3_16*") (pintype "bidirectional"))
      (node (ref "U1") (pin "16_") (pinfunction "D3_16_") (pintype "bidirectional"))
      (node (ref "U1") (pin "1_16") (pinfunction "D3_1_16") (pintype "bidirectional"))
    )
    (net (code "43") (name "Net-(SJ11-Pad1)") (class "Default")
      (node (ref "SJ11") (pin "1") (pinfunction "1_1") (pintype "passive"))
      (node (ref "U1") (pin "15") (pinfunction "D2_15") (pintype "bidirectional"))
      (node (ref "U1") (pin "15*") (pinfunction "D2_15*") (pintype "bidirectional"))
      (node (ref "U1") (pin "15_") (pinfunction "D2_15_") (pintype "bidirectional"))
      (node (ref "U1") (pin "1_15") (pinfunction "D2_1_15") (pintype "bidirectional"))
    )
    (net (code "44") (name "Net-(SJ12-Pad1)") (class "Default")
      (node (ref "SJ12") (pin "1") (pinfunction "1_1") (pintype "passive"))
      (node (ref "U1") (pin "14") (pinfunction "D1_14") (pintype "bidirectional"))
      (node (ref "U1") (pin "14*") (pinfunction "D1_14*") (pintype "bidirectional"))
      (node (ref "U1") (pin "14_") (pinfunction "D1_14_") (pintype "bidirectional"))
      (node (ref "U1") (pin "1_14") (pinfunction "D1_1_14") (pintype "bidirectional"))
    )
    (net (code "45") (name "Net-(SJ13-Pad1)") (class "Default")
      (node (ref "SJ13") (pin "1") (pinfunction "1_1") (pintype "passive"))
      (node (ref "U1") (pin "13") (pinfunction "D0_13") (pintype "bidirectional"))
      (node (ref "U1") (pin "13*") (pinfunction "D0_13*") (pintype "bidirectional"))
      (node (ref "U1") (pin "13_") (pinfunction "D0_13_") (pintype "bidirectional"))
      (node (ref "U1") (pin "1_13") (pinfunction "D0_1_13") (pintype "bidirectional"))
    )
    (net (code "46") (name "Net-(U1-~{RST}-Pad1_23)") (class "Default")
      (node (ref "U1") (pin "1_23") (pinfunction "~{RST}_1_23") (pintype "bidirectional"))
      (node (ref "U1") (pin "23") (pinfunction "~{RST}_23") (pintype "bidirectional"))
      (node (ref "U1") (pin "23*") (pinfunction "~{RST}_23*") (pintype "bidirectional"))
      (node (ref "U1") (pin "23_") (pinfunction "~{RST}_23_") (pintype "bidirectional"))
    )
    (net (code "47") (name "Net-(U4-CLKIN{slash}XTAL2)") (class "Default")
      (node (ref "C23") (pin "1") (pinfunction "1_1") (pintype "passive"))
      (node (ref "R23") (pin "2") (pinfunction "2_2") (pintype "passive"))
      (node (ref "U4") (pin "2") (pinfunction "CLKIN/XTAL2_2") (pintype "bidirectional"))
      (node (ref "Y1") (pin "1") (pinfunction "1_1") (pintype "passive"))
    )
    (net (code "48") (name "Net-(U4-VDDA)") (class "Default")
      (node (ref "C15") (pin "1") (pinfunction "1_1") (pintype "passive"))
      (node (ref "C16") (pin "1") (pinfunction "1_1") (pintype "passive"))
      (node (ref "C19") (pin "1") (pinfunction "1_1") (pintype "passive"))
      (node (ref "U4") (pin "21") (pinfunction "VDDA_21") (pintype "bidirectional"))
    )
    (net (code "49") (name "Net-(U4-VDDD)") (class "Default")
      (node (ref "C12") (pin "1") (pinfunction "1_1") (pintype "passive"))
      (node (ref "C13") (pin "1") (pinfunction "1_1") (pintype "passive"))
      (node (ref "C14") (pin "1") (pinfunction "1_1") (pintype "passive"))
      (node (ref "U4") (pin "27") (pinfunction "VDDD_27") (pintype "bidirectional"))
    )
    (net (code "50") (name "Net-(U4-VREF1)") (class "Default")
      (node (ref "C20") (pin "1") (pinfunction "1_1") (pintype "passive"))
      (node (ref "C21") (pin "1") (pinfunction "1_1") (pintype "passive"))
      (node (ref "U4") (pin "17") (pinfunction "VREF1_17") (pintype "bidirectional"))
    )
    (net (code "51") (name "Net-(U4-VREF2)") (class "Default")
      (node (ref "C17") (pin "1") (pinfunction "1_1") (pintype "passive"))
      (node (ref "C18") (pin "1") (pinfunction "1_1") (pintype "passive"))
      (node (ref "U4") (pin "19") (pinfunction "VREF2_19") (pintype "bidirectional"))
    )
    (net (code "52") (name "Net-(U4-XTAL1)") (class "Default")
      (node (ref "C22") (pin "1") (pinfunction "1_1") (pintype "passive"))
      (node (ref "R23") (pin "1") (pinfunction "1_1") (pintype "passive"))
      (node (ref "U4") (pin "3") (pinfunction "XTAL1_3") (pintype "bidirectional"))
      (node (ref "Y1") (pin "2") (pinfunction "2_2") (pintype "passive"))
    )
    (net (code "53") (name "PWR_CS") (class "Default")
      (node (ref "R21") (pin "1") (pinfunction "1_1") (pintype "passive"))
      (node (ref "SJ3") (pin "1") (pinfunction "1_1") (pintype "passive"))
      (node (ref "U4") (pin "29") (pinfunction "SCS_29") (pintype "bidirectional"))
    )
    (net (code "54") (name "PWR_EN") (class "Default")
      (node (ref "R22") (pin "1") (pinfunction "1_1") (pintype "passive"))
      (node (ref "SJ6") (pin "2") (pinfunction "2_2") (pintype "passive"))
      (node (ref "U4") (pin "8") (pinfunction "EN_8") (pintype "bidirectional"))
    )
    (net (code "55") (name "PWR_INT1") (class "Default")
      (node (ref "SJ2") (pin "1") (pinfunction "1_1") (pintype "passive"))
      (node (ref "U4") (pin "6") (pinfunction "INT1_6") (pintype "bidirectional"))
    )
    (net (code "56") (name "PWR_INT2") (class "Default")
      (node (ref "SJ1") (pin "1") (pinfunction "1_1") (pintype "passive"))
      (node (ref "U4") (pin "7") (pinfunction "INT2_7") (pintype "bidirectional"))
    )
    (net (code "57") (name "PWR_LED1") (class "Default")
      (node (ref "SJ9") (pin "2") (pinfunction "2_2") (pintype "passive"))
      (node (ref "U4") (pin "4") (pinfunction "LED1_4") (pintype "bidirectional"))
    )
    (net (code "58") (name "PWR_LED2") (class "Default")
      (node (ref "SJ10") (pin "2") (pinfunction "2_2") (pintype "passive"))
      (node (ref "U4") (pin "5") (pinfunction "LED2_5") (pintype "bidirectional"))
    )
    (net (code "59") (name "PWR_SYN") (class "Default")
      (node (ref "SJ7") (pin "2") (pinfunction "2_2") (pintype "passive"))
      (node (ref "U4") (pin "28") (pinfunction "SYN_28") (pintype "bidirectional"))
    )
    (net (code "60") (name "PWR_ZCR") (class "Default")
      (node (ref "SJ13") (pin "2") (pinfunction "2_2") (pintype "passive"))
      (node (ref "U4") (pin "1") (pinfunction "CLKOUT/ZCR_1") (pintype "bidirectional"))
    )
    (net (code "61") (name "UART_RX") (class "Default")
      (node (ref "U1") (pin "1_4") (pinfunction "RX_1_4") (pintype "bidirectional"))
      (node (ref "U1") (pin "4") (pinfunction "RX_4") (pintype "bidirectional"))
      (node (ref "U1") (pin "4*") (pinfunction "RX_4*") (pintype "bidirectional"))
      (node (ref "U1") (pin "4_") (pinfunction "RX_4_") (pintype "bidirectional"))
    )
    (net (code "62") (name "UART_TX") (class "Default")
      (node (ref "U1") (pin "1_3") (pinfunction "TX_1_3") (pintype "bidirectional"))
      (node (ref "U1") (pin "3") (pinfunction "TX_3") (pintype "bidirectional"))
      (node (ref "U1") (pin "3*") (pinfunction "TX_3*") (pintype "bidirectional"))
      (node (ref "U1") (pin "3_") (pinfunction "TX_3_") (pintype "bidirectional"))
    )
    (net (code "63") (name "USD_CD") (class "Default")
      (node (ref "SJ8") (pin "2") (pinfunction "2_2") (pintype "passive"))
      (node (ref "U2") (pin "CD1") (pinfunction "CD1_CD1") (pintype "bidirectional"))
    )
    (net (code "64") (name "USD_CS") (class "Default")
      (node (ref "R2") (pin "2") (pinfunction "2_2") (pintype "passive"))
      (node (ref "SJ5") (pin "1") (pinfunction "1_1") (pintype "passive"))
      (node (ref "U2") (pin "2") (pinfunction "CS_2") (pintype "bidirectional"))
    )
    (net (code "65") (name "VBAT") (class "Default")
      (node (ref "C2") (pin "1") (pinfunction "1_1") (pintype "passive"))
      (node (ref "D2") (pin "C") (pinfunction "C_C") (pintype "passive"))
      (node (ref "U1") (pin "1_22") (pinfunction "VBAT_1_22") (pintype "power_in"))
      (node (ref "U1") (pin "22") (pinfunction "VBAT_22") (pintype "power_in"))
      (node (ref "U1") (pin "22*") (pinfunction "VBAT_22*") (pintype "power_in"))
      (node (ref "U1") (pin "22_") (pinfunction "VBAT_22_") (pintype "power_in"))
    )
    (net (code "66") (name "VDD") (class "Default")
      (node (ref "C10") (pin "1") (pinfunction "1_1") (pintype "passive"))
      (node (ref "C11") (pin "1") (pinfunction "+_1") (pintype "passive"))
      (node (ref "C8") (pin "1") (pinfunction "1_1") (pintype "passive"))
      (node (ref "C9") (pin "1") (pinfunction "1_1") (pintype "passive"))
      (node (ref "L1") (pin "2") (pinfunction "2_2") (pintype "passive"))
      (node (ref "R21") (pin "2") (pinfunction "2_2") (pintype "passive"))
      (node (ref "U4") (pin "23") (pinfunction "VCC_23") (pintype "bidirectional"))
    )
    (net (code "67") (name "VIN1+") (class "Default")
      (node (ref "C4") (pin "1") (pinfunction "1_1") (pintype "passive"))
      (node (ref "R8") (pin "1") (pinfunction "1_1") (pintype "passive"))
      (node (ref "R9") (pin "2") (pinfunction "2_2") (pintype "passive"))
      (node (ref "U4") (pin "9") (pinfunction "VIP1_9") (pintype "bidirectional"))
    )
    (net (code "68") (name "VIN2+") (class "Default")
      (node (ref "C5") (pin "1") (pinfunction "1_1") (pintype "passive"))
      (node (ref "R13") (pin "1") (pinfunction "1_1") (pintype "passive"))
      (node (ref "R14") (pin "2") (pinfunction "2_2") (pintype "passive"))
      (node (ref "U4") (pin "16") (pinfunction "VIP2_16") (pintype "bidirectional"))
    )
    (net (code "69") (name "unconnected-(JP1-PadD+)") (class "Default")
      (node (ref "JP1") (pin "D+") (pinfunction "D+_D+") (pintype "bidirectional"))
    )
    (net (code "70") (name "unconnected-(JP1-PadD-)") (class "Default")
      (node (ref "JP1") (pin "D-") (pinfunction "D-_D-") (pintype "bidirectional"))
    )
    (net (code "71") (name "unconnected-(JP3-RIGHT-PadRING)") (class "Default")
      (node (ref "JP3") (pin "RING") (pinfunction "RIGHT_RING") (pintype "bidirectional"))
    )
    (net (code "72") (name "unconnected-(JP4-RIGHT-PadRING)") (class "Default")
      (node (ref "JP4") (pin "RING") (pinfunction "RIGHT_RING") (pintype "bidirectional"))
    )
    (net (code "73") (name "unconnected-(U2-NC-Pad1)") (class "Default")
      (node (ref "U2") (pin "1") (pinfunction "NC_1") (pintype "bidirectional"))
    )
    (net (code "74") (name "unconnected-(U2-PadCD2)") (class "Default")
      (node (ref "U2") (pin "CD2") (pinfunction "CD2_CD2") (pintype "bidirectional"))
    )
    (net (code "75") (name "unconnected-(U2-RSV-Pad8)") (class "Default")
      (node (ref "U2") (pin "8") (pinfunction "RSV_8") (pintype "bidirectional"))
    )
  )
)
